# v3c_pcb.net
KiCad netlist of a schematic drawn in EAGLE
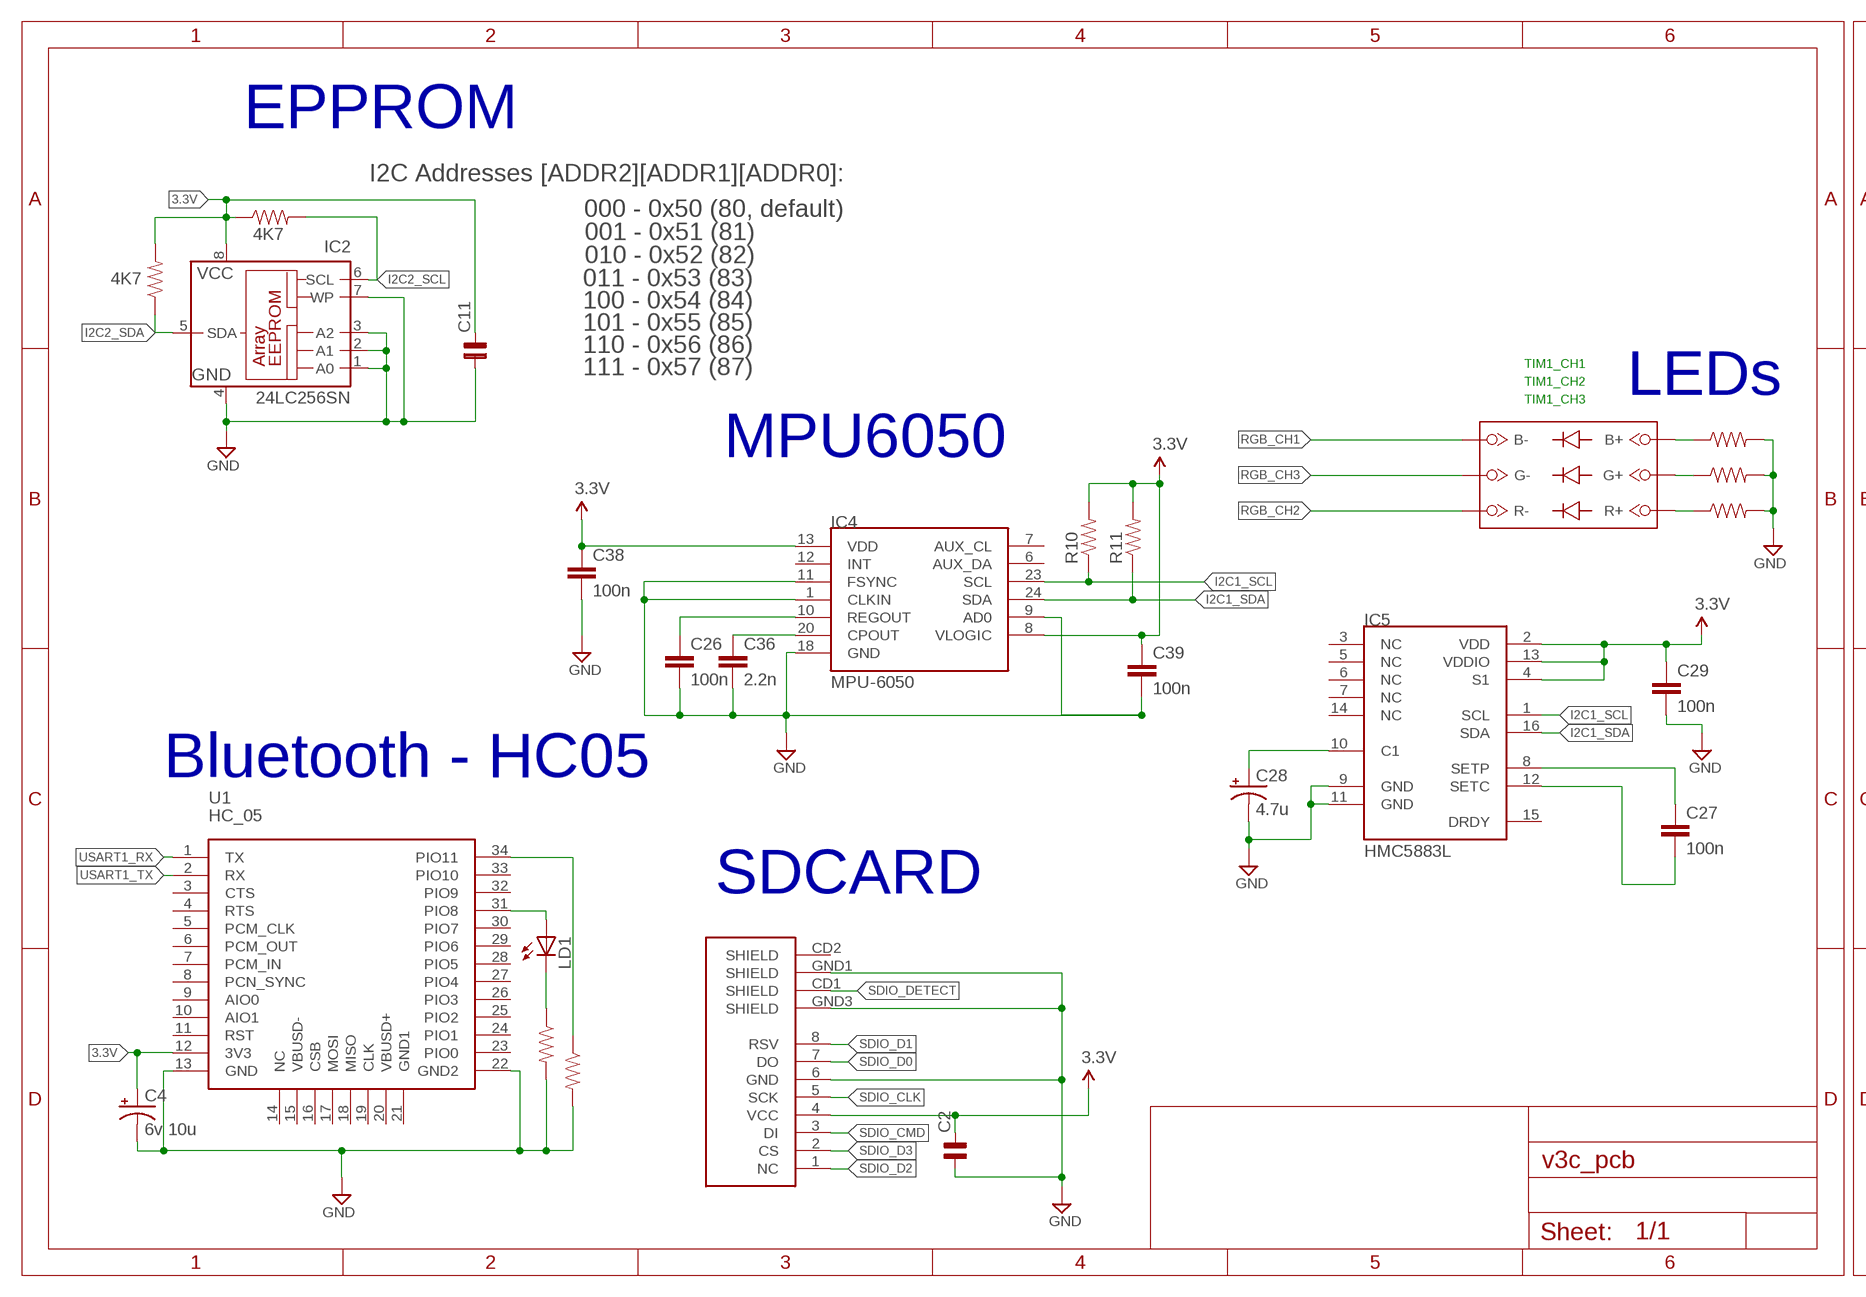
[diagram p0: schematic, sheet 1, part 1 of 2]
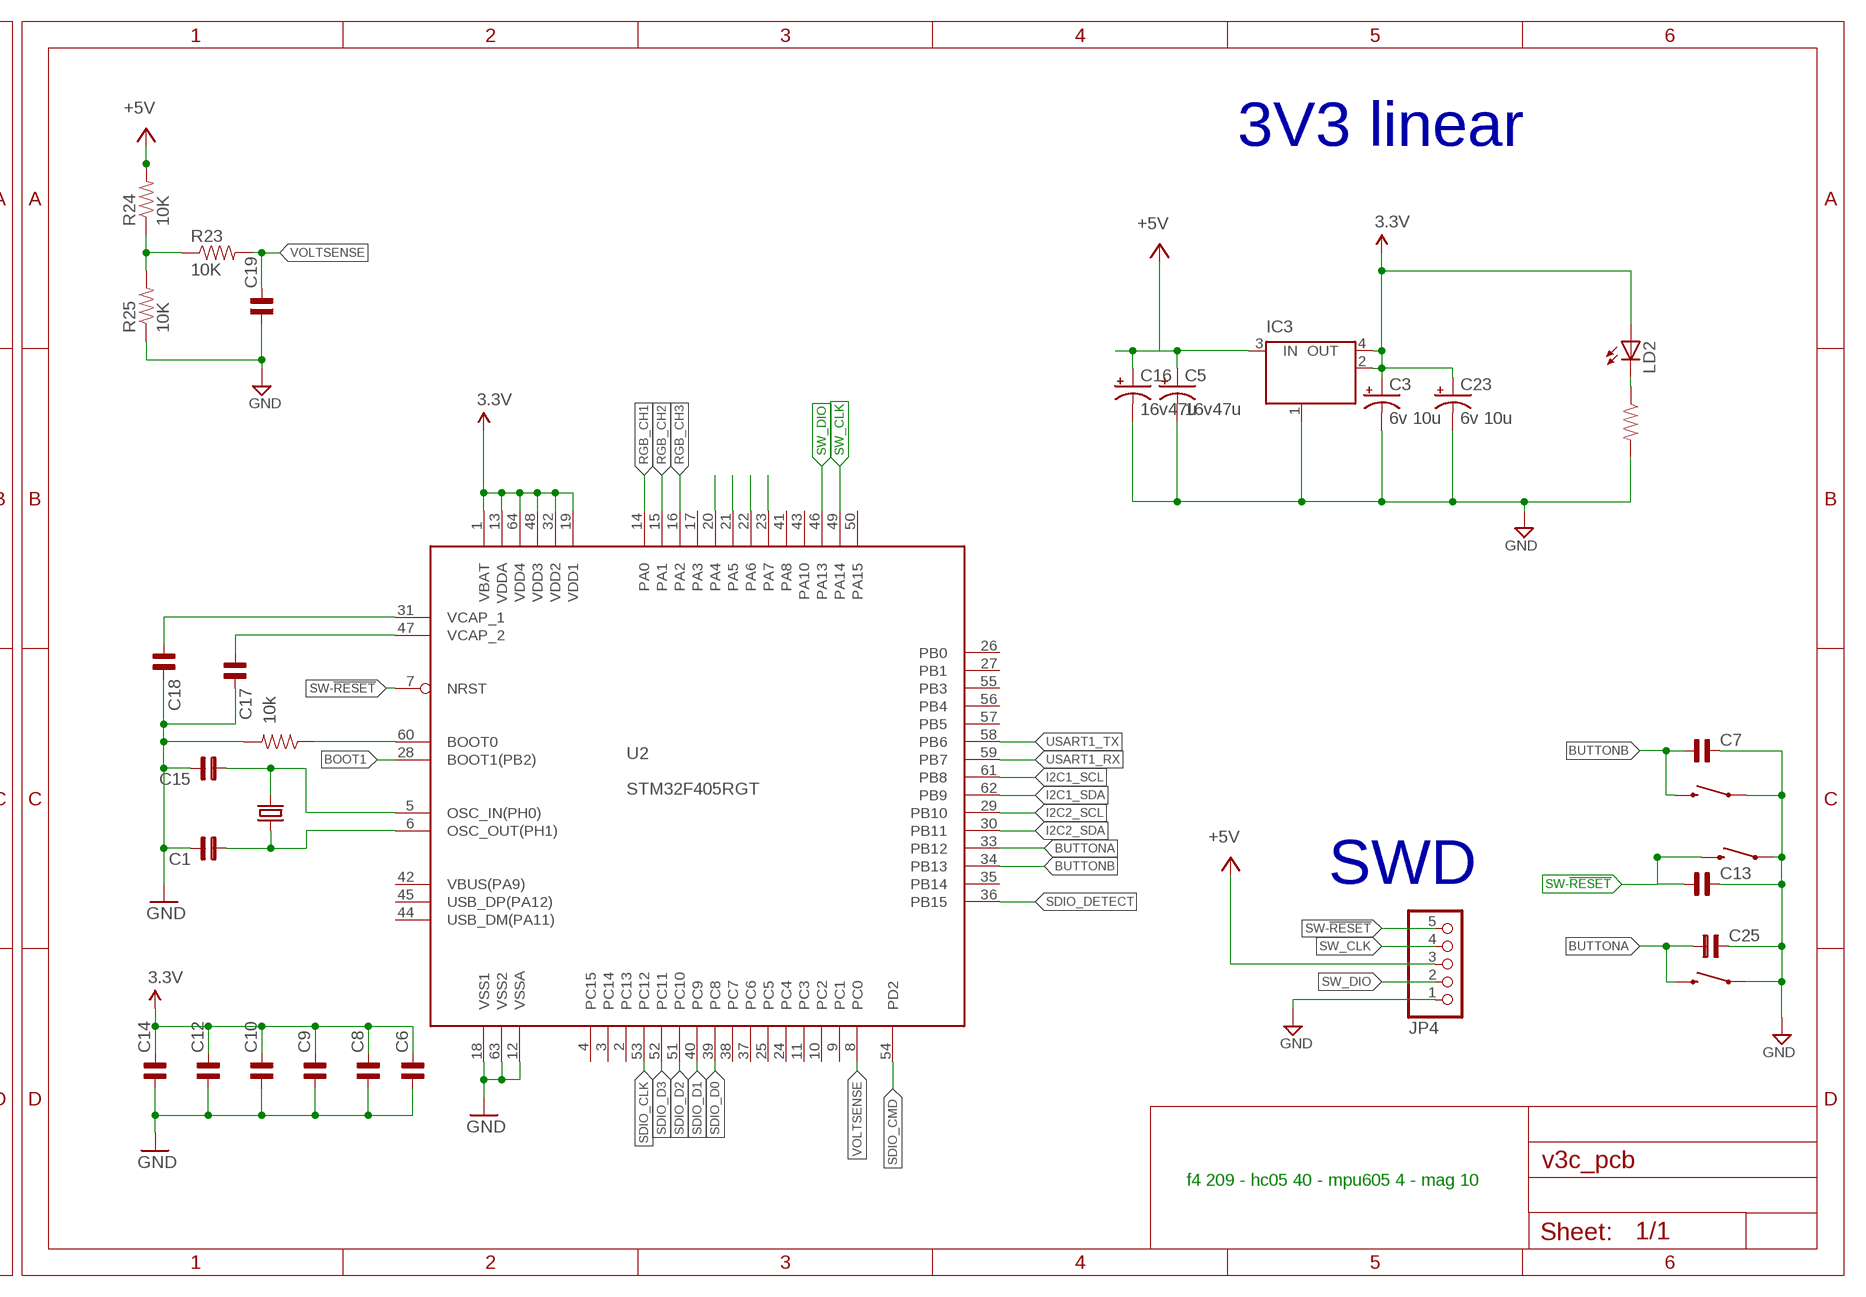
[diagram p1: schematic, sheet 1, part 2 of 2]

(export (version "E")
  (design (tool "Eeschema 10.0.6"))
  (components
    (comp (ref "C1")
      (value "C-NP-SMD-0603")
      (footprint "eagle-import:C-0603")
      (libsource (lib "eagle-import") (part "C-NP-SMD-0603"))
    )
    (comp (ref "C2")
      (value "C-NP-SMD-0603")
      (footprint "eagle-import:C-0603")
      (libsource (lib "eagle-import") (part "C-NP-SMD-0603"))
    )
    (comp (ref "C3")
      (value "6v 10u")
      (footprint "eagle-import:SMC_C")
      (libsource (lib "eagle-import") (part "CPOL-USSMCC"))
    )
    (comp (ref "C4")
      (value "6v 10u")
      (footprint "eagle-import:SMC_A")
      (libsource (lib "eagle-import") (part "CPOL-USSMCA"))
    )
    (comp (ref "C5")
      (value "16v47u")
      (footprint "eagle-import:SMC_C")
      (libsource (lib "eagle-import") (part "CPOL-USSMCC"))
    )
    (comp (ref "C6")
      (value "C-NP-SMD-0603")
      (footprint "eagle-import:C-0603")
      (libsource (lib "eagle-import") (part "C-NP-SMD-0603"))
    )
    (comp (ref "C7")
      (value "C-NP-SMD-0603")
      (footprint "eagle-import:C-0603")
      (libsource (lib "eagle-import") (part "C-NP-SMD-0603"))
    )
    (comp (ref "C8")
      (value "C-NP-SMD-0603")
      (footprint "eagle-import:C-0603")
      (libsource (lib "eagle-import") (part "C-NP-SMD-0603"))
    )
    (comp (ref "C9")
      (value "C-NP-SMD-0603")
      (footprint "eagle-import:C-0603")
      (libsource (lib "eagle-import") (part "C-NP-SMD-0603"))
    )
    (comp (ref "C10")
      (value "C-NP-SMD-0603")
      (footprint "eagle-import:C-0603")
      (libsource (lib "eagle-import") (part "C-NP-SMD-0603"))
    )
    (comp (ref "C11")
      (value "C-NP-SMD-0603")
      (footprint "eagle-import:C-0603")
      (libsource (lib "eagle-import") (part "C-NP-SMD-0603"))
    )
    (comp (ref "C12")
      (value "C-NP-SMD-0603")
      (footprint "eagle-import:C-0603")
      (libsource (lib "eagle-import") (part "C-NP-SMD-0603"))
    )
    (comp (ref "C13")
      (value "C-NP-SMD-0603")
      (footprint "eagle-import:C-0603")
      (libsource (lib "eagle-import") (part "C-NP-SMD-0603"))
    )
    (comp (ref "C14")
      (value "C-NP-SMD-0603")
      (footprint "eagle-import:C-0603")
      (libsource (lib "eagle-import") (part "C-NP-SMD-0603"))
    )
    (comp (ref "C15")
      (value "C-NP-SMD-0603")
      (footprint "eagle-import:C-0603")
      (libsource (lib "eagle-import") (part "C-NP-SMD-0603"))
    )
    (comp (ref "C16")
      (value "16v47u")
      (footprint "eagle-import:SMC_C")
      (libsource (lib "eagle-import") (part "CPOL-USSMCC"))
    )
    (comp (ref "C17")
      (value "C-NP-SMD-0603")
      (footprint "eagle-import:C-0603")
      (libsource (lib "eagle-import") (part "C-NP-SMD-0603"))
    )
    (comp (ref "C18")
      (value "C-NP-SMD-0603")
      (footprint "eagle-import:C-0603")
      (libsource (lib "eagle-import") (part "C-NP-SMD-0603"))
    )
    (comp (ref "C19")
      (value "C-NP-SMD-0603")
      (footprint "eagle-import:C-0603")
      (libsource (lib "eagle-import") (part "C-NP-SMD-0603"))
    )
    (comp (ref "C23")
      (value "6v 10u")
      (footprint "eagle-import:SMC_C")
      (libsource (lib "eagle-import") (part "CPOL-USSMCC"))
    )
    (comp (ref "C25")
      (value "C-NP-SMD-0603")
      (footprint "eagle-import:C-0603")
      (libsource (lib "eagle-import") (part "C-NP-SMD-0603"))
    )
    (comp (ref "C26")
      (value "100n")
      (footprint "eagle-import:SPARKFUN_0603-CAP")
      (libsource (lib "eagle-import") (part "SPARKFUN_CAP0603-CAP"))
    )
    (comp (ref "C27")
      (value "100n")
      (footprint "eagle-import:SPARKFUN_0603-CAP")
      (libsource (lib "eagle-import") (part "SPARKFUN_CAP0603-CAP"))
    )
    (comp (ref "C28")
      (value "4.7u")
      (footprint "eagle-import:SMC_A")
      (libsource (lib "eagle-import") (part "CPOL-USSMCA"))
    )
    (comp (ref "C29")
      (value "100n")
      (footprint "eagle-import:SPARKFUN_0603-CAP")
      (libsource (lib "eagle-import") (part "SPARKFUN_CAP0603-CAP"))
    )
    (comp (ref "C36")
      (value "2.2n")
      (footprint "eagle-import:SPARKFUN_0603-CAP")
      (libsource (lib "eagle-import") (part "SPARKFUN_CAP0603-CAP"))
    )
    (comp (ref "C38")
      (value "100n")
      (footprint "eagle-import:SPARKFUN_0603-CAP")
      (libsource (lib "eagle-import") (part "SPARKFUN_CAP0603-CAP"))
    )
    (comp (ref "C39")
      (value "100n")
      (footprint "eagle-import:SPARKFUN_0603-CAP")
      (libsource (lib "eagle-import") (part "SPARKFUN_CAP0603-CAP"))
    )
    (comp (ref "IC2")
      (value "24LC256SN")
      (footprint "eagle-import:SO-08")
      (fields (field (name "MF") "MICROCHIP") (field (name "MPN") "24LC256-I/SN"))
      (libsource (lib "eagle-import") (part "24SNLC256"))
    )
    (comp (ref "IC3")
      (value "LINEAR_MC33269ST-3.3T3")
      (footprint "eagle-import:LINEAR_SOT223")
      (libsource (lib "eagle-import") (part "LINEAR_MC33269ST-3.3T3"))
    )
    (comp (ref "IC4")
      (value "MPU-6050")
      (footprint "eagle-import:TESTING_QFN-24-4MM2")
      (libsource (lib "eagle-import") (part "TESTING_MPU-6050-1"))
    )
    (comp (ref "IC5")
      (value "HMC5883L")
      (footprint "eagle-import:SPARKFUN_16LPCC")
      (libsource (lib "eagle-import") (part "SPARKFUN_HMC5883LSMD"))
    )
    (comp (ref "JP4")
      (value "PINHD-1X5_2.54-90°")
      (footprint "eagle-import:1X05_90")
      (libsource (lib "eagle-import") (part "PINHD-1X5_2.54-90°"))
    )
    (comp (ref "LD1")
      (value "LEDCHIPLED_0603")
      (footprint "eagle-import:CHIPLED_0603")
      (libsource (lib "eagle-import") (part "LEDCHIPLED_0603"))
    )
    (comp (ref "LD2")
      (value "LEDCHIPLED_0603")
      (footprint "eagle-import:CHIPLED_0603")
      (libsource (lib "eagle-import") (part "LEDCHIPLED_0603"))
    )
    (comp (ref "R1")
      (value "10K")
      (footprint "eagle-import:SPARKFUN_0603-RES")
      (libsource (lib "eagle-import") (part "Robotech_RCL_SPARKFUN_RESISTOR0603-RES"))
    )
    (comp (ref "R2")
      (value "10K")
      (footprint "eagle-import:SPARKFUN_0603-RES")
      (libsource (lib "eagle-import") (part "Robotech_RCL_SPARKFUN_RESISTOR0603-RES"))
    )
    (comp (ref "R3")
      (value "10K")
      (footprint "eagle-import:SPARKFUN_0603-RES")
      (libsource (lib "eagle-import") (part "Robotech_RCL_SPARKFUN_RESISTOR0603-RES"))
    )
    (comp (ref "R5")
      (value "10K")
      (footprint "eagle-import:SPARKFUN_0603-RES")
      (libsource (lib "eagle-import") (part "Robotech_RCL_SPARKFUN_RESISTOR0603-RES"))
    )
    (comp (ref "R6")
      (value "10K")
      (footprint "eagle-import:SPARKFUN_0603-RES")
      (libsource (lib "eagle-import") (part "Robotech_RCL_SPARKFUN_RESISTOR0603-RES"))
    )
    (comp (ref "R7")
      (value "10k")
      (footprint "eagle-import:SPARKFUN_0603-RES")
      (libsource (lib "eagle-import") (part "Robotech_RCL_SPARKFUN_RESISTOR0603-RES"))
    )
    (comp (ref "R9")
      (value "10K")
      (footprint "eagle-import:SPARKFUN_0603-RES")
      (libsource (lib "eagle-import") (part "Robotech_RCL_SPARKFUN_RESISTOR0603-RES"))
    )
    (comp (ref "R10")
      (value "SPARKFUN_RESISTOR0603-RES")
      (footprint "eagle-import:SPARKFUN_0603-RES")
      (libsource (lib "eagle-import") (part "SPARKFUN_RESISTOR0603-RES"))
    )
    (comp (ref "R11")
      (value "SPARKFUN_RESISTOR0603-RES")
      (footprint "eagle-import:SPARKFUN_0603-RES")
      (libsource (lib "eagle-import") (part "SPARKFUN_RESISTOR0603-RES"))
    )
    (comp (ref "R15")
      (value "4K7")
      (footprint "eagle-import:SPARKFUN_0603-RES")
      (libsource (lib "eagle-import") (part "Robotech_RCL_SPARKFUN_RESISTOR0603-RES"))
    )
    (comp (ref "R16")
      (value "4K7")
      (footprint "eagle-import:SPARKFUN_0603-RES")
      (libsource (lib "eagle-import") (part "Robotech_RCL_SPARKFUN_RESISTOR0603-RES"))
    )
    (comp (ref "R23")
      (value "10K")
      (footprint "eagle-import:SPARKFUN_0603-RES")
      (libsource (lib "eagle-import") (part "Robotech_RCL_SPARKFUN_RESISTOR0603-RES"))
    )
    (comp (ref "R24")
      (value "10K")
      (footprint "eagle-import:SPARKFUN_0603-RES")
      (libsource (lib "eagle-import") (part "Robotech_RCL_SPARKFUN_RESISTOR0603-RES"))
    )
    (comp (ref "R25")
      (value "10K")
      (footprint "eagle-import:SPARKFUN_0603-RES")
      (libsource (lib "eagle-import") (part "Robotech_RCL_SPARKFUN_RESISTOR0603-RES"))
    )
    (comp (ref "S1")
      (value "RESET")
      (footprint "eagle-import:TACTILE-SWITCH-1101NE")
      (fields (field (name "PARTNO") "EVQ-P7J01P"))
      (libsource (lib "eagle-import") (part "SWITCH-MOMENTARY-2-SMD-1101NE"))
    )
    (comp (ref "S2")
      (value "RESET")
      (footprint "eagle-import:TACTILE-SWITCH-1101NE")
      (fields (field (name "PARTNO") "EVQ-P7J01P"))
      (libsource (lib "eagle-import") (part "SWITCH-MOMENTARY-2-SMD-1101NE"))
    )
    (comp (ref "S4")
      (value "RESET")
      (footprint "eagle-import:TACTILE-SWITCH-1101NE")
      (fields (field (name "PARTNO") "EVQ-P7J01P"))
      (libsource (lib "eagle-import") (part "SWITCH-MOMENTARY-2-SMD-1101NE"))
    )
    (comp (ref "SDCARD2")
      (value "microSD Socket")
      (footprint "eagle-import:MICRO-SD-SOCKET-PP")
      (libsource (lib "eagle-import") (part "USD-SOCKETNEW"))
    )
    (comp (ref "U$12")
      (value "RGB_LED")
      (footprint "eagle-import:SMD")
      (libsource (lib "eagle-import") (part "RGB_LED"))
    )
    (comp (ref "U1")
      (value "HC_05")
      (footprint "eagle-import:BLUETOOTH_SMD")
      (libsource (lib "eagle-import") (part "HC_05"))
    )
    (comp (ref "U2")
      (value "STM32F405RGT")
      (footprint "eagle-import:LQFP64")
      (libsource (lib "eagle-import") (part "STM32F405RGT"))
    )
    (comp (ref "Y2")
      (value "CRYSTALHC49US")
      (footprint "eagle-import:HC49US")
      (libsource (lib "eagle-import") (part "CRYSTALHC49US"))
    )
  )
  (nets
    (net (code "1") (name "+5V") (class "Default")
      (node (ref "C16") (pin "+") (pinfunction "+_+") (pintype "passive"))
      (node (ref "C5") (pin "+") (pinfunction "+_+") (pintype "passive"))
      (node (ref "IC3") (pin "3") (pinfunction "IN_3") (pintype "input"))
      (node (ref "JP4") (pin "3") (pinfunction "3_3") (pintype "passive"))
      (node (ref "R24") (pin "2") (pinfunction "2_2") (pintype "passive"))
    )
    (net (code "2") (name "/SW-~{RESET}") (class "Default")
      (node (ref "C13") (pin "1") (pinfunction "1_1") (pintype "passive"))
      (node (ref "JP4") (pin "5") (pinfunction "5_5") (pintype "passive"))
      (node (ref "S1") (pin "P$2") (pinfunction "2_P$2") (pintype "passive"))
      (node (ref "U2") (pin "7") (pinfunction "NRST_7") (pintype "input"))
    )
    (net (code "3") (name "3.3V") (class "Default")
      (node (ref "C10") (pin "2") (pinfunction "2_2") (pintype "passive"))
      (node (ref "C11") (pin "2") (pinfunction "2_2") (pintype "passive"))
      (node (ref "C12") (pin "2") (pinfunction "2_2") (pintype "passive"))
      (node (ref "C14") (pin "2") (pinfunction "2_2") (pintype "passive"))
      (node (ref "C2") (pin "2") (pinfunction "2_2") (pintype "passive"))
      (node (ref "C23") (pin "+") (pinfunction "+_+") (pintype "passive"))
      (node (ref "C29") (pin "1") (pinfunction "1_1") (pintype "passive"))
      (node (ref "C3") (pin "+") (pinfunction "+_+") (pintype "passive"))
      (node (ref "C38") (pin "1") (pinfunction "1_1") (pintype "passive"))
      (node (ref "C39") (pin "1") (pinfunction "1_1") (pintype "passive"))
      (node (ref "C4") (pin "+") (pinfunction "+_+") (pintype "passive"))
      (node (ref "C6") (pin "2") (pinfunction "2_2") (pintype "passive"))
      (node (ref "C8") (pin "2") (pinfunction "2_2") (pintype "passive"))
      (node (ref "C9") (pin "2") (pinfunction "2_2") (pintype "passive"))
      (node (ref "IC2") (pin "8") (pinfunction "VCC_8") (pintype "power_in"))
      (node (ref "IC3") (pin "2") (pinfunction "OUT_2") (pintype "passive"))
      (node (ref "IC3") (pin "4") (pinfunction "OUT_4") (pintype "passive"))
      (node (ref "IC4") (pin "13") (pinfunction "VDD_13") (pintype "bidirectional"))
      (node (ref "IC4") (pin "8") (pinfunction "VLOGIC_8") (pintype "bidirectional"))
      (node (ref "IC5") (pin "13") (pinfunction "VDDIO_13") (pintype "bidirectional"))
      (node (ref "IC5") (pin "2") (pinfunction "VDD_2") (pintype "bidirectional"))
      (node (ref "IC5") (pin "4") (pinfunction "S1_4") (pintype "bidirectional"))
      (node (ref "LD2") (pin "A") (pinfunction "A_A") (pintype "passive"))
      (node (ref "R10") (pin "2") (pinfunction "2_2") (pintype "passive"))
      (node (ref "R11") (pin "2") (pinfunction "2_2") (pintype "passive"))
      (node (ref "R15") (pin "1") (pinfunction "1_1") (pintype "passive"))
      (node (ref "R16") (pin "2") (pinfunction "2_2") (pintype "passive"))
      (node (ref "SDCARD2") (pin "4") (pinfunction "VCC_4") (pintype "bidirectional"))
      (node (ref "U1") (pin "12") (pinfunction "3V3_12") (pintype "bidirectional"))
      (node (ref "U2") (pin "1") (pinfunction "VBAT_1") (pintype "power_in"))
      (node (ref "U2") (pin "13") (pinfunction "VDDA_13") (pintype "power_in"))
      (node (ref "U2") (pin "19") (pinfunction "VDD1_19") (pintype "power_in"))
      (node (ref "U2") (pin "32") (pinfunction "VDD2_32") (pintype "power_in"))
      (node (ref "U2") (pin "48") (pinfunction "VDD3_48") (pintype "power_in"))
      (node (ref "U2") (pin "64") (pinfunction "VDD4_64") (pintype "power_in"))
    )
    (net (code "4") (name "BOOT1") (class "Default")
      (node (ref "U2") (pin "28") (pinfunction "BOOT1(PB2)_28") (pintype "input"))
    )
    (net (code "5") (name "BUTTONA") (class "Default")
      (node (ref "C25") (pin "1") (pinfunction "1_1") (pintype "passive"))
      (node (ref "S2") (pin "P$2") (pinfunction "2_P$2") (pintype "passive"))
      (node (ref "U2") (pin "33") (pinfunction "PB12_33") (pintype "bidirectional"))
    )
    (net (code "6") (name "BUTTONB") (class "Default")
      (node (ref "C7") (pin "1") (pinfunction "1_1") (pintype "passive"))
      (node (ref "S4") (pin "P$2") (pinfunction "2_P$2") (pintype "passive"))
      (node (ref "U2") (pin "34") (pinfunction "PB13_34") (pintype "bidirectional"))
    )
    (net (code "7") (name "GND") (class "Default")
      (node (ref "C1") (pin "2") (pinfunction "2_2") (pintype "passive"))
      (node (ref "C10") (pin "1") (pinfunction "1_1") (pintype "passive"))
      (node (ref "C11") (pin "1") (pinfunction "1_1") (pintype "passive"))
      (node (ref "C12") (pin "1") (pinfunction "1_1") (pintype "passive"))
      (node (ref "C13") (pin "2") (pinfunction "2_2") (pintype "passive"))
      (node (ref "C14") (pin "1") (pinfunction "1_1") (pintype "passive"))
      (node (ref "C15") (pin "2") (pinfunction "2_2") (pintype "passive"))
      (node (ref "C16") (pin "-") (pinfunction "-_-") (pintype "passive"))
      (node (ref "C17") (pin "2") (pinfunction "2_2") (pintype "passive"))
      (node (ref "C18") (pin "2") (pinfunction "2_2") (pintype "passive"))
      (node (ref "C19") (pin "1") (pinfunction "1_1") (pintype "passive"))
      (node (ref "C2") (pin "1") (pinfunction "1_1") (pintype "passive"))
      (node (ref "C23") (pin "-") (pinfunction "-_-") (pintype "passive"))
      (node (ref "C25") (pin "2") (pinfunction "2_2") (pintype "passive"))
      (node (ref "C26") (pin "2") (pinfunction "2_2") (pintype "passive"))
      (node (ref "C28") (pin "-") (pinfunction "-_-") (pintype "passive"))
      (node (ref "C29") (pin "2") (pinfunction "2_2") (pintype "passive"))
      (node (ref "C3") (pin "-") (pinfunction "-_-") (pintype "passive"))
      (node (ref "C36") (pin "2") (pinfunction "2_2") (pintype "passive"))
      (node (ref "C38") (pin "2") (pinfunction "2_2") (pintype "passive"))
      (node (ref "C39") (pin "2") (pinfunction "2_2") (pintype "passive"))
      (node (ref "C4") (pin "-") (pinfunction "-_-") (pintype "passive"))
      (node (ref "C5") (pin "-") (pinfunction "-_-") (pintype "passive"))
      (node (ref "C6") (pin "1") (pinfunction "1_1") (pintype "passive"))
      (node (ref "C7") (pin "2") (pinfunction "2_2") (pintype "passive"))
      (node (ref "C8") (pin "1") (pinfunction "1_1") (pintype "passive"))
      (node (ref "C9") (pin "1") (pinfunction "1_1") (pintype "passive"))
      (node (ref "IC2") (pin "1") (pinfunction "A0_1") (pintype "input"))
      (node (ref "IC2") (pin "2") (pinfunction "A1_2") (pintype "input"))
      (node (ref "IC2") (pin "3") (pinfunction "A2_3") (pintype "input"))
      (node (ref "IC2") (pin "4") (pinfunction "GND_4") (pintype "power_in"))
      (node (ref "IC2") (pin "7") (pinfunction "WP_7") (pintype "input"))
      (node (ref "IC3") (pin "1") (pinfunction "GND/ADJ_1") (pintype "input"))
      (node (ref "IC4") (pin "1") (pinfunction "CLKIN_1") (pintype "bidirectional"))
      (node (ref "IC4") (pin "11") (pinfunction "FSYNC_11") (pintype "bidirectional"))
      (node (ref "IC4") (pin "18") (pinfunction "GND_18") (pintype "bidirectional"))
      (node (ref "IC4") (pin "9") (pinfunction "AD0_9") (pintype "bidirectional"))
      (node (ref "IC5") (pin "11") (pinfunction "GND_11") (pintype "bidirectional"))
      (node (ref "IC5") (pin "9") (pinfunction "GND_9") (pintype "bidirectional"))
      (node (ref "JP4") (pin "1") (pinfunction "1_1") (pintype "passive"))
      (node (ref "R1") (pin "2") (pinfunction "2_2") (pintype "passive"))
      (node (ref "R2") (pin "2") (pinfunction "2_2") (pintype "passive"))
      (node (ref "R25") (pin "1") (pinfunction "1_1") (pintype "passive"))
      (node (ref "R3") (pin "2") (pinfunction "2_2") (pintype "passive"))
      (node (ref "R5") (pin "2") (pinfunction "2_2") (pintype "passive"))
      (node (ref "R6") (pin "2") (pinfunction "2_2") (pintype "passive"))
      (node (ref "R7") (pin "2") (pinfunction "2_2") (pintype "passive"))
      (node (ref "R9") (pin "2") (pinfunction "2_2") (pintype "passive"))
      (node (ref "S1") (pin "P$1") (pinfunction "1_P$1") (pintype "passive"))
      (node (ref "S2") (pin "P$1") (pinfunction "1_P$1") (pintype "passive"))
      (node (ref "S4") (pin "P$1") (pinfunction "1_P$1") (pintype "passive"))
      (node (ref "SDCARD2") (pin "6") (pinfunction "GND_6") (pintype "bidirectional"))
      (node (ref "SDCARD2") (pin "GND1") (pinfunction "SHIELD_GND1") (pintype "bidirectional"))
      (node (ref "SDCARD2") (pin "GND3") (pinfunction "SHIELD_GND3") (pintype "bidirectional"))
      (node (ref "U1") (pin "13") (pinfunction "GND_13") (pintype "bidirectional"))
      (node (ref "U1") (pin "22") (pinfunction "GND2_22") (pintype "bidirectional"))
      (node (ref "U2") (pin "12") (pinfunction "VSSA_12") (pintype "power_in"))
      (node (ref "U2") (pin "18") (pinfunction "VSS1_18") (pintype "power_in"))
      (node (ref "U2") (pin "63") (pinfunction "VSS2_63") (pintype "power_in"))
    )
    (net (code "8") (name "I2C1_SCL") (class "Default")
      (node (ref "IC4") (pin "23") (pinfunction "SCL_23") (pintype "bidirectional"))
      (node (ref "IC5") (pin "1") (pinfunction "SCL_1") (pintype "bidirectional"))
      (node (ref "R10") (pin "1") (pinfunction "1_1") (pintype "passive"))
      (node (ref "U2") (pin "61") (pinfunction "PB8_61") (pintype "bidirectional"))
    )
    (net (code "9") (name "I2C1_SDA") (class "Default")
      (node (ref "IC4") (pin "24") (pinfunction "SDA_24") (pintype "bidirectional"))
      (node (ref "IC5") (pin "16") (pinfunction "SDA_16") (pintype "bidirectional"))
      (node (ref "R11") (pin "1") (pinfunction "1_1") (pintype "passive"))
      (node (ref "U2") (pin "62") (pinfunction "PB9_62") (pintype "bidirectional"))
    )
    (net (code "10") (name "I2C2_SCL") (class "Default")
      (node (ref "IC2") (pin "6") (pinfunction "SCL_6") (pintype "input"))
      (node (ref "R15") (pin "2") (pinfunction "2_2") (pintype "passive"))
      (node (ref "U2") (pin "29") (pinfunction "PB10_29") (pintype "bidirectional"))
    )
    (net (code "11") (name "I2C2_SDA") (class "Default")
      (node (ref "IC2") (pin "5") (pinfunction "SDA_5") (pintype "bidirectional"))
      (node (ref "R16") (pin "1") (pinfunction "1_1") (pintype "passive"))
      (node (ref "U2") (pin "30") (pinfunction "PB11_30") (pintype "bidirectional"))
    )
    (net (code "12") (name "Net-(IC4-CPOUT)") (class "Default")
      (node (ref "C36") (pin "1") (pinfunction "1_1") (pintype "passive"))
      (node (ref "IC4") (pin "20") (pinfunction "CPOUT_20") (pintype "bidirectional"))
    )
    (net (code "13") (name "Net-(IC4-REGOUT)") (class "Default")
      (node (ref "C26") (pin "1") (pinfunction "1_1") (pintype "passive"))
      (node (ref "IC4") (pin "10") (pinfunction "REGOUT_10") (pintype "bidirectional"))
    )
    (net (code "14") (name "Net-(IC5-C1)") (class "Default")
      (node (ref "C28") (pin "+") (pinfunction "+_+") (pintype "passive"))
      (node (ref "IC5") (pin "10") (pinfunction "C1_10") (pintype "bidirectional"))
    )
    (net (code "15") (name "Net-(IC5-SETC)") (class "Default")
      (node (ref "C27") (pin "2") (pinfunction "2_2") (pintype "passive"))
      (node (ref "IC5") (pin "12") (pinfunction "SETC_12") (pintype "bidirectional"))
    )
    (net (code "16") (name "Net-(IC5-SETP)") (class "Default")
      (node (ref "C27") (pin "1") (pinfunction "1_1") (pintype "passive"))
      (node (ref "IC5") (pin "8") (pinfunction "SETP_8") (pintype "bidirectional"))
    )
    (net (code "17") (name "Net-(LD1-PadC)") (class "Default")
      (node (ref "LD1") (pin "C") (pinfunction "C_C") (pintype "passive"))
      (node (ref "R9") (pin "1") (pinfunction "1_1") (pintype "passive"))
    )
    (net (code "18") (name "Net-(LD2-PadC)") (class "Default")
      (node (ref "LD2") (pin "C") (pinfunction "C_C") (pintype "passive"))
      (node (ref "R1") (pin "1") (pinfunction "1_1") (pintype "passive"))
    )
    (net (code "19") (name "Net-(R2-Pad1)") (class "Default")
      (node (ref "R2") (pin "1") (pinfunction "1_1") (pintype "passive"))
      (node (ref "U$12") (pin "B+") (pinfunction "B+_B+") (pintype "bidirectional"))
    )
    (net (code "20") (name "Net-(R3-Pad1)") (class "Default")
      (node (ref "R3") (pin "1") (pinfunction "1_1") (pintype "passive"))
      (node (ref "U$12") (pin "G+") (pinfunction "G+_G+") (pintype "bidirectional"))
    )
    (net (code "21") (name "Net-(R6-Pad1)") (class "Default")
      (node (ref "R6") (pin "1") (pinfunction "1_1") (pintype "passive"))
      (node (ref "U$12") (pin "R+") (pinfunction "R+_R+") (pintype "bidirectional"))
    )
    (net (code "22") (name "Net-(R23-Pad1)") (class "Default")
      (node (ref "R23") (pin "1") (pinfunction "1_1") (pintype "passive"))
      (node (ref "R24") (pin "1") (pinfunction "1_1") (pintype "passive"))
      (node (ref "R25") (pin "2") (pinfunction "2_2") (pintype "passive"))
    )
    (net (code "23") (name "Net-(U1-PIO8)") (class "Default")
      (node (ref "LD1") (pin "A") (pinfunction "A_A") (pintype "passive"))
      (node (ref "U1") (pin "31") (pinfunction "PIO8_31") (pintype "bidirectional"))
    )
    (net (code "24") (name "Net-(U1-PIO11)") (class "Default")
      (node (ref "R5") (pin "1") (pinfunction "1_1") (pintype "passive"))
      (node (ref "U1") (pin "34") (pinfunction "PIO11_34") (pintype "bidirectional"))
    )
    (net (code "25") (name "Net-(U2-BOOT0)") (class "Default")
      (node (ref "R7") (pin "1") (pinfunction "1_1") (pintype "passive"))
      (node (ref "U2") (pin "60") (pinfunction "BOOT0_60") (pintype "input"))
    )
    (net (code "26") (name "Net-(U2-OSC_IN(PH0))") (class "Default")
      (node (ref "C15") (pin "1") (pinfunction "1_1") (pintype "passive"))
      (node (ref "U2") (pin "5") (pinfunction "OSC_IN(PH0)_5") (pintype "bidirectional"))
      (node (ref "Y2") (pin "2") (pinfunction "2_2") (pintype "passive"))
    )
    (net (code "27") (name "Net-(U2-OSC_OUT(PH1))") (class "Default")
      (node (ref "C1") (pin "1") (pinfunction "1_1") (pintype "passive"))
      (node (ref "U2") (pin "6") (pinfunction "OSC_OUT(PH1)_6") (pintype "bidirectional"))
      (node (ref "Y2") (pin "1") (pinfunction "1_1") (pintype "passive"))
    )
    (net (code "28") (name "Net-(U2-VCAP_1)") (class "Default")
      (node (ref "C18") (pin "1") (pinfunction "1_1") (pintype "passive"))
      (node (ref "U2") (pin "31") (pinfunction "VCAP_1_31") (pintype "bidirectional"))
    )
    (net (code "29") (name "Net-(U2-VCAP_2)") (class "Default")
      (node (ref "C17") (pin "1") (pinfunction "1_1") (pintype "passive"))
      (node (ref "U2") (pin "47") (pinfunction "VCAP_2_47") (pintype "bidirectional"))
    )
    (net (code "30") (name "RGB_CH1") (class "Default")
      (node (ref "U$12") (pin "B-") (pinfunction "B-_B-") (pintype "bidirectional"))
      (node (ref "U2") (pin "14") (pinfunction "PA0_14") (pintype "bidirectional"))
    )
    (net (code "31") (name "RGB_CH2") (class "Default")
      (node (ref "U$12") (pin "R-") (pinfunction "R-_R-") (pintype "bidirectional"))
      (node (ref "U2") (pin "15") (pinfunction "PA1_15") (pintype "bidirectional"))
    )
    (net (code "32") (name "RGB_CH3") (class "Default")
      (node (ref "U$12") (pin "G-") (pinfunction "G-_G-") (pintype "bidirectional"))
      (node (ref "U2") (pin "16") (pinfunction "PA2_16") (pintype "bidirectional"))
    )
    (net (code "33") (name "SDIO_CLK") (class "Default")
      (node (ref "SDCARD2") (pin "5") (pinfunction "SCK_5") (pintype "bidirectional"))
      (node (ref "U2") (pin "53") (pinfunction "PC12_53") (pintype "bidirectional"))
    )
    (net (code "34") (name "SDIO_CMD") (class "Default")
      (node (ref "SDCARD2") (pin "3") (pinfunction "DI_3") (pintype "bidirectional"))
      (node (ref "U2") (pin "54") (pinfunction "PD2_54") (pintype "bidirectional"))
    )
    (net (code "35") (name "SDIO_D0") (class "Default")
      (node (ref "SDCARD2") (pin "7") (pinfunction "DO_7") (pintype "bidirectional"))
      (node (ref "U2") (pin "39") (pinfunction "PC8_39") (pintype "bidirectional"))
    )
    (net (code "36") (name "SDIO_D1") (class "Default")
      (node (ref "SDCARD2") (pin "8") (pinfunction "RSV_8") (pintype "bidirectional"))
      (node (ref "U2") (pin "40") (pinfunction "PC9_40") (pintype "bidirectional"))
    )
    (net (code "37") (name "SDIO_D2") (class "Default")
      (node (ref "SDCARD2") (pin "1") (pinfunction "NC_1") (pintype "bidirectional"))
      (node (ref "U2") (pin "51") (pinfunction "PC10_51") (pintype "bidirectional"))
    )
    (net (code "38") (name "SDIO_D3") (class "Default")
      (node (ref "SDCARD2") (pin "2") (pinfunction "CS_2") (pintype "bidirectional"))
      (node (ref "U2") (pin "52") (pinfunction "PC11_52") (pintype "bidirectional"))
    )
    (net (code "39") (name "SDIO_DETECT") (class "Default")
      (node (ref "SDCARD2") (pin "CD1") (pinfunction "SHIELD_CD1") (pintype "bidirectional"))
      (node (ref "U2") (pin "36") (pinfunction "PB15_36") (pintype "bidirectional"))
    )
    (net (code "40") (name "SW_CLK") (class "Default")
      (node (ref "JP4") (pin "4") (pinfunction "4_4") (pintype "passive"))
      (node (ref "U2") (pin "49") (pinfunction "PA14_49") (pintype "bidirectional"))
    )
    (net (code "41") (name "SW_DIO") (class "Default")
      (node (ref "JP4") (pin "2") (pinfunction "2_2") (pintype "passive"))
      (node (ref "U2") (pin "46") (pinfunction "PA13_46") (pintype "bidirectional"))
    )
    (net (code "42") (name "USART1_RX") (class "Default")
      (node (ref "U1") (pin "1") (pinfunction "TX_1") (pintype "bidirectional"))
      (node (ref "U2") (pin "59") (pinfunction "PB7_59") (pintype "bidirectional"))
    )
    (net (code "43") (name "USART1_TX") (class "Default")
      (node (ref "U1") (pin "2") (pinfunction "RX_2") (pintype "bidirectional"))
      (node (ref "U2") (pin "58") (pinfunction "PB6_58") (pintype "bidirectional"))
    )
    (net (code "44") (name "VOLTSENSE") (class "Default")
      (node (ref "C19") (pin "2") (pinfunction "2_2") (pintype "passive"))
      (node (ref "R23") (pin "2") (pinfunction "2_2") (pintype "passive"))
      (node (ref "U2") (pin "8") (pinfunction "PC0_8") (pintype "bidirectional"))
    )
    (net (code "45") (name "unconnected-(IC4-AUX_CL-Pad7)") (class "Default")
      (node (ref "IC4") (pin "7") (pinfunction "AUX_CL_7") (pintype "bidirectional"))
    )
    (net (code "46") (name "unconnected-(IC4-AUX_DA-Pad6)") (class "Default")
      (node (ref "IC4") (pin "6") (pinfunction "AUX_DA_6") (pintype "bidirectional"))
    )
    (net (code "47") (name "unconnected-(IC4-INT-Pad12)") (class "Default")
      (node (ref "IC4") (pin "12") (pinfunction "INT_12") (pintype "bidirectional"))
    )
    (net (code "48") (name "unconnected-(IC5-DRDY-Pad15)") (class "Default")
      (node (ref "IC5") (pin "15") (pinfunction "DRDY_15") (pintype "bidirectional"))
    )
    (net (code "49") (name "unconnected-(IC5-NC-Pad3)") (class "Default")
      (node (ref "IC5") (pin "3") (pinfunction "NC_3") (pintype "bidirectional"))
    )
    (net (code "50") (name "unconnected-(IC5-NC-Pad5)") (class "Default")
      (node (ref "IC5") (pin "5") (pinfunction "NC_5") (pintype "bidirectional"))
    )
    (net (code "51") (name "unconnected-(IC5-NC-Pad6)") (class "Default")
      (node (ref "IC5") (pin "6") (pinfunction "NC_6") (pintype "bidirectional"))
    )
    (net (code "52") (name "unconnected-(IC5-NC-Pad7)") (class "Default")
      (node (ref "IC5") (pin "7") (pinfunction "NC_7") (pintype "bidirectional"))
    )
    (net (code "53") (name "unconnected-(IC5-NC-Pad14)") (class "Default")
      (node (ref "IC5") (pin "14") (pinfunction "NC_14") (pintype "bidirectional"))
    )
    (net (code "54") (name "unconnected-(SDCARD2-SHIELD-PadCD2)") (class "Default")
      (node (ref "SDCARD2") (pin "CD2") (pinfunction "SHIELD_CD2") (pintype "bidirectional"))
    )
    (net (code "55") (name "unconnected-(U1-AIO0-Pad9)") (class "Default")
      (node (ref "U1") (pin "9") (pinfunction "AIO0_9") (pintype "bidirectional"))
    )
    (net (code "56") (name "unconnected-(U1-AIO1-Pad10)") (class "Default")
      (node (ref "U1") (pin "10") (pinfunction "AIO1_10") (pintype "bidirectional"))
    )
    (net (code "57") (name "unconnected-(U1-CLK-Pad19)") (class "Default")
      (node (ref "U1") (pin "19") (pinfunction "CLK_19") (pintype "bidirectional"))
    )
    (net (code "58") (name "unconnected-(U1-CSB-Pad16)") (class "Default")
      (node (ref "U1") (pin "16") (pinfunction "CSB_16") (pintype "bidirectional"))
    )
    (net (code "59") (name "unconnected-(U1-CTS-Pad3)") (class "Default")
      (node (ref "U1") (pin "3") (pinfunction "CTS_3") (pintype "bidirectional"))
    )
    (net (code "60") (name "unconnected-(U1-GND1-Pad21)") (class "Default")
      (node (ref "U1") (pin "21") (pinfunction "GND1_21") (pintype "bidirectional"))
    )
    (net (code "61") (name "unconnected-(U1-MISO-Pad18)") (class "Default")
      (node (ref "U1") (pin "18") (pinfunction "MISO_18") (pintype "bidirectional"))
    )
    (net (code "62") (name "unconnected-(U1-MOSI-Pad17)") (class "Default")
      (node (ref "U1") (pin "17") (pinfunction "MOSI_17") (pintype "bidirectional"))
    )
    (net (code "63") (name "unconnected-(U1-NC-Pad14)") (class "Default")
      (node (ref "U1") (pin "14") (pinfunction "NC_14") (pintype "bidirectional"))
    )
    (net (code "64") (name "unconnected-(U1-PCM_CLK-Pad5)") (class "Default")
      (node (ref "U1") (pin "5") (pinfunction "PCM_CLK_5") (pintype "bidirectional"))
    )
    (net (code "65") (name "unconnected-(U1-PCM_IN-Pad7)") (class "Default")
      (node (ref "U1") (pin "7") (pinfunction "PCM_IN_7") (pintype "bidirectional"))
    )
    (net (code "66") (name "unconnected-(U1-PCM_OUT-Pad6)") (class "Default")
      (node (ref "U1") (pin "6") (pinfunction "PCM_OUT_6") (pintype "bidirectional"))
    )
    (net (code "67") (name "unconnected-(U1-PCN_SYNC-Pad8)") (class "Default")
      (node (ref "U1") (pin "8") (pinfunction "PCN_SYNC_8") (pintype "bidirectional"))
    )
    (net (code "68") (name "unconnected-(U1-PIO0-Pad23)") (class "Default")
      (node (ref "U1") (pin "23") (pinfunction "PIO0_23") (pintype "bidirectional"))
    )
    (net (code "69") (name "unconnected-(U1-PIO1-Pad24)") (class "Default")
      (node (ref "U1") (pin "24") (pinfunction "PIO1_24") (pintype "bidirectional"))
    )
    (net (code "70") (name "unconnected-(U1-PIO2-Pad25)") (class "Default")
      (node (ref "U1") (pin "25") (pinfunction "PIO2_25") (pintype "bidirectional"))
    )
    (net (code "71") (name "unconnected-(U1-PIO3-Pad26)") (class "Default")
      (node (ref "U1") (pin "26") (pinfunction "PIO3_26") (pintype "bidirectional"))
    )
    (net (code "72") (name "unconnected-(U1-PIO4-Pad27)") (class "Default")
      (node (ref "U1") (pin "27") (pinfunction "PIO4_27") (pintype "bidirectional"))
    )
    (net (code "73") (name "unconnected-(U1-PIO5-Pad28)") (class "Default")
      (node (ref "U1") (pin "28") (pinfunction "PIO5_28") (pintype "bidirectional"))
    )
    (net (code "74") (name "unconnected-(U1-PIO6-Pad29)") (class "Default")
      (node (ref "U1") (pin "29") (pinfunction "PIO6_29") (pintype "bidirectional"))
    )
    (net (code "75") (name "unconnected-(U1-PIO7-Pad30)") (class "Default")
      (node (ref "U1") (pin "30") (pinfunction "PIO7_30") (pintype "bidirectional"))
    )
    (net (code "76") (name "unconnected-(U1-PIO9-Pad32)") (class "Default")
      (node (ref "U1") (pin "32") (pinfunction "PIO9_32") (pintype "bidirectional"))
    )
    (net (code "77") (name "unconnected-(U1-PIO10-Pad33)") (class "Default")
      (node (ref "U1") (pin "33") (pinfunction "PIO10_33") (pintype "bidirectional"))
    )
    (net (code "78") (name "unconnected-(U1-RST-Pad11)") (class "Default")
      (node (ref "U1") (pin "11") (pinfunction "RST_11") (pintype "bidirectional"))
    )
    (net (code "79") (name "unconnected-(U1-RTS-Pad4)") (class "Default")
      (node (ref "U1") (pin "4") (pinfunction "RTS_4") (pintype "bidirectional"))
    )
    (net (code "80") (name "unconnected-(U1-VBUSD+-Pad20)") (class "Default")
      (node (ref "U1") (pin "20") (pinfunction "VBUSD+_20") (pintype "bidirectional"))
    )
    (net (code "81") (name "unconnected-(U1-VBUSD--Pad15)") (class "Default")
      (node (ref "U1") (pin "15") (pinfunction "VBUSD-_15") (pintype "bidirectional"))
    )
    (net (code "82") (name "unconnected-(U2-PA3-Pad17)") (class "Default")
      (node (ref "U2") (pin "17") (pinfunction "PA3_17") (pintype "bidirectional"))
    )
    (net (code "83") (name "unconnected-(U2-PA4-Pad20)") (class "Default")
      (node (ref "U2") (pin "20") (pinfunction "PA4_20") (pintype "bidirectional"))
    )
    (net (code "84") (name "unconnected-(U2-PA5-Pad21)") (class "Default")
      (node (ref "U2") (pin "21") (pinfunction "PA5_21") (pintype "bidirectional"))
    )
    (net (code "85") (name "unconnected-(U2-PA6-Pad22)") (class "Default")
      (node (ref "U2") (pin "22") (pinfunction "PA6_22") (pintype "bidirectional"))
    )
    (net (code "86") (name "unconnected-(U2-PA7-Pad23)") (class "Default")
      (node (ref "U2") (pin "23") (pinfunction "PA7_23") (pintype "bidirectional"))
    )
    (net (code "87") (name "unconnected-(U2-PA8-Pad41)") (class "Default")
      (node (ref "U2") (pin "41") (pinfunction "PA8_41") (pintype "bidirectional"))
    )
    (net (code "88") (name "unconnected-(U2-PA10-Pad43)") (class "Default")
      (node (ref "U2") (pin "43") (pinfunction "PA10_43") (pintype "bidirectional"))
    )
    (net (code "89") (name "unconnected-(U2-PA15-Pad50)") (class "Default")
      (node (ref "U2") (pin "50") (pinfunction "PA15_50") (pintype "bidirectional"))
    )
    (net (code "90") (name "unconnected-(U2-PB0-Pad26)") (class "Default")
      (node (ref "U2") (pin "26") (pinfunction "PB0_26") (pintype "bidirectional"))
    )
    (net (code "91") (name "unconnected-(U2-PB1-Pad27)") (class "Default")
      (node (ref "U2") (pin "27") (pinfunction "PB1_27") (pintype "bidirectional"))
    )
    (net (code "92") (name "unconnected-(U2-PB3-Pad55)") (class "Default")
      (node (ref "U2") (pin "55") (pinfunction "PB3_55") (pintype "bidirectional"))
    )
    (net (code "93") (name "unconnected-(U2-PB4-Pad56)") (class "Default")
      (node (ref "U2") (pin "56") (pinfunction "PB4_56") (pintype "bidirectional"))
    )
    (net (code "94") (name "unconnected-(U2-PB5-Pad57)") (class "Default")
      (node (ref "U2") (pin "57") (pinfunction "PB5_57") (pintype "bidirectional"))
    )
    (net (code "95") (name "unconnected-(U2-PB14-Pad35)") (class "Default")
      (node (ref "U2") (pin "35") (pinfunction "PB14_35") (pintype "bidirectional"))
    )
    (net (code "96") (name "unconnected-(U2-PC1-Pad9)") (class "Default")
      (node (ref "U2") (pin "9") (pinfunction "PC1_9") (pintype "bidirectional"))
    )
    (net (code "97") (name "unconnected-(U2-PC2-Pad10)") (class "Default")
      (node (ref "U2") (pin "10") (pinfunction "PC2_10") (pintype "bidirectional"))
    )
    (net (code "98") (name "unconnected-(U2-PC3-Pad11)") (class "Default")
      (node (ref "U2") (pin "11") (pinfunction "PC3_11") (pintype "bidirectional"))
    )
    (net (code "99") (name "unconnected-(U2-PC4-Pad24)") (class "Default")
      (node (ref "U2") (pin "24") (pinfunction "PC4_24") (pintype "bidirectional"))
    )
    (net (code "100") (name "unconnected-(U2-PC5-Pad25)") (class "Default")
      (node (ref "U2") (pin "25") (pinfunction "PC5_25") (pintype "bidirectional"))
    )
    (net (code "101") (name "unconnected-(U2-PC6-Pad37)") (class "Default")
      (node (ref "U2") (pin "37") (pinfunction "PC6_37") (pintype "bidirectional"))
    )
    (net (code "102") (name "unconnected-(U2-PC7-Pad38)") (class "Default")
      (node (ref "U2") (pin "38") (pinfunction "PC7_38") (pintype "bidirectional"))
    )
    (net (code "103") (name "unconnected-(U2-PC13-Pad2)") (class "Default")
      (node (ref "U2") (pin "2") (pinfunction "PC13_2") (pintype "bidirectional"))
    )
    (net (code "104") (name "unconnected-(U2-PC14-Pad3)") (class "Default")
      (node (ref "U2") (pin "3") (pinfunction "PC14_3") (pintype "bidirectional"))
    )
    (net (code "105") (name "unconnected-(U2-PC15-Pad4)") (class "Default")
      (node (ref "U2") (pin "4") (pinfunction "PC15_4") (pintype "bidirectional"))
    )
    (net (code "106") (name "unconnected-(U2-USB_DM(PA11)-Pad44)") (class "Default")
      (node (ref "U2") (pin "44") (pinfunction "USB_DM(PA11)_44") (pintype "bidirectional"))
    )
    (net (code "107") (name "unconnected-(U2-USB_DP(PA12)-Pad45)") (class "Default")
      (node (ref "U2") (pin "45") (pinfunction "USB_DP(PA12)_45") (pintype "bidirectional"))
    )
    (net (code "108") (name "unconnected-(U2-VBUS(PA9)-Pad42)") (class "Default")
      (node (ref "U2") (pin "42") (pinfunction "VBUS(PA9)_42") (pintype "bidirectional"))
    )
  )
)
